# Cisco-Console-CP2102-Piggyback-v2.net
KiCad netlist of a schematic drawn in EAGLE
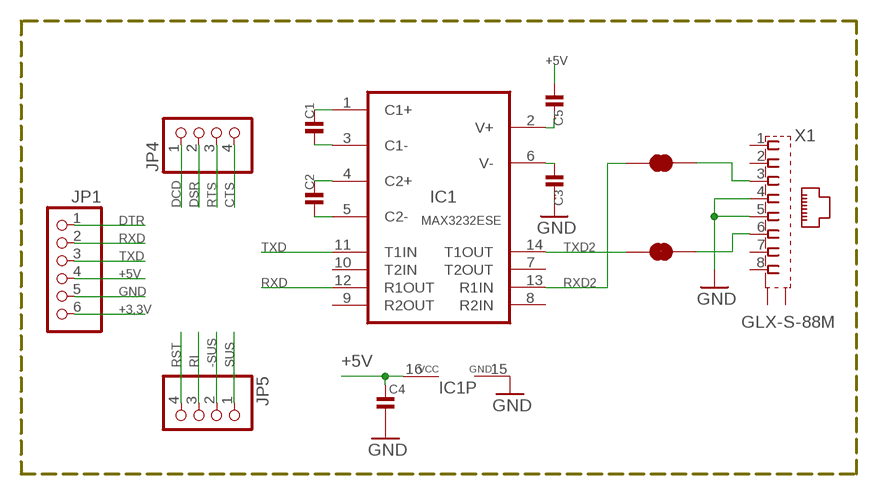
[diagram p0: schematic, sheet 1]

(export (version "E")
  (design (tool "Eeschema 10.0.6"))
  (components
    (comp (ref "C1")
      (value "MICROBUILDER_CAP_CERAMIC0402")
      (footprint "eagle-import:MICROBUILDER_0402")
      (libsource (lib "eagle-import") (part "MICROBUILDER_CAP_CERAMIC0402"))
    )
    (comp (ref "C2")
      (value "MICROBUILDER_CAP_CERAMIC0402")
      (footprint "eagle-import:MICROBUILDER_0402")
      (libsource (lib "eagle-import") (part "MICROBUILDER_CAP_CERAMIC0402"))
    )
    (comp (ref "C3")
      (value "MICROBUILDER_CAP_CERAMIC0402")
      (footprint "eagle-import:MICROBUILDER_0402")
      (libsource (lib "eagle-import") (part "MICROBUILDER_CAP_CERAMIC0402"))
    )
    (comp (ref "C4")
      (value "MICROBUILDER_CAP_CERAMIC0402")
      (footprint "eagle-import:MICROBUILDER_0402")
      (libsource (lib "eagle-import") (part "MICROBUILDER_CAP_CERAMIC0402"))
    )
    (comp (ref "C5")
      (value "MICROBUILDER_CAP_CERAMIC0402")
      (footprint "eagle-import:MICROBUILDER_0402")
      (libsource (lib "eagle-import") (part "MICROBUILDER_CAP_CERAMIC0402"))
    )
    (comp (ref "IC1")
      (value "MAX3232ESE")
      (footprint "eagle-import:SO16")
      (fields (field (name "MF") "MAXIM"))
      (libsource (lib "eagle-import") (part "MAX3232SEE"))
    )
    (comp (ref "JP1")
      (value "PINHD-1X6")
      (footprint "eagle-import:1X06")
      (libsource (lib "eagle-import") (part "PINHD-1X6"))
    )
    (comp (ref "JP4")
      (value "PINHD-1X4")
      (footprint "eagle-import:1X04")
      (libsource (lib "eagle-import") (part "PINHD-1X4"))
    )
    (comp (ref "JP5")
      (value "PINHD-1X4")
      (footprint "eagle-import:1X04")
      (libsource (lib "eagle-import") (part "PINHD-1X4"))
    )
    (comp (ref "JP6")
      (value "JUMPER-SMT_2_NC_TRACE_NO-SILK")
      (footprint "eagle-import:SMT-JUMPER_2_NC_TRACE_NO-SILK")
      (libsource (lib "eagle-import") (part "JUMPER-SMT_2_NC_TRACE_NO-SILK"))
    )
    (comp (ref "JP9")
      (value "JUMPER-SMT_2_NC_TRACE_NO-SILK")
      (footprint "eagle-import:SMT-JUMPER_2_NC_TRACE_NO-SILK")
      (libsource (lib "eagle-import") (part "JUMPER-SMT_2_NC_TRACE_NO-SILK"))
    )
    (comp (ref "X1")
      (value "GLX-S-88M")
      (footprint "eagle-import:GLX-S-88M")
      (libsource (lib "eagle-import") (part "GLX-S-88M"))
    )
  )
  (nets
    (net (code "1") (name "/+3,3V") (class "Default")
      (node (ref "JP1") (pin "6") (pinfunction "6_6") (pintype "passive"))
    )
    (net (code "2") (name "/+5V") (class "Default")
      (node (ref "C4") (pin "1") (pinfunction "P$1_1") (pintype "passive"))
      (node (ref "C5") (pin "1") (pinfunction "P$1_1") (pintype "passive"))
      (node (ref "IC1") (pin "16") (pinfunction "VCC_16") (pintype "power_in"))
      (node (ref "JP1") (pin "4") (pinfunction "4_4") (pintype "passive"))
    )
    (net (code "3") (name "/-SUS") (class "Default")
      (node (ref "JP5") (pin "2") (pinfunction "2_2") (pintype "passive"))
    )
    (net (code "4") (name "/CTS") (class "Default")
      (node (ref "JP4") (pin "4") (pinfunction "4_4") (pintype "passive"))
    )
    (net (code "5") (name "/DCD") (class "Default")
      (node (ref "JP4") (pin "1") (pinfunction "1_1") (pintype "passive"))
    )
    (net (code "6") (name "/DSR") (class "Default")
      (node (ref "JP4") (pin "2") (pinfunction "2_2") (pintype "passive"))
    )
    (net (code "7") (name "/DTR") (class "Default")
      (node (ref "JP1") (pin "1") (pinfunction "1_1") (pintype "passive"))
    )
    (net (code "8") (name "/RI") (class "Default")
      (node (ref "JP5") (pin "3") (pinfunction "3_3") (pintype "passive"))
    )
    (net (code "9") (name "/RST") (class "Default")
      (node (ref "JP5") (pin "4") (pinfunction "4_4") (pintype "passive"))
    )
    (net (code "10") (name "/RTS") (class "Default")
      (node (ref "JP4") (pin "3") (pinfunction "3_3") (pintype "passive"))
    )
    (net (code "11") (name "/RXD") (class "Default")
      (node (ref "IC1") (pin "12") (pinfunction "R1OUT_12") (pintype "output"))
      (node (ref "JP1") (pin "2") (pinfunction "2_2") (pintype "passive"))
    )
    (net (code "12") (name "/RXD2") (class "Default")
      (node (ref "IC1") (pin "13") (pinfunction "R1IN_13") (pintype "input"))
      (node (ref "JP6") (pin "1") (pinfunction "1_1") (pintype "passive"))
    )
    (net (code "13") (name "/SUS") (class "Default")
      (node (ref "JP5") (pin "1") (pinfunction "1_1") (pintype "passive"))
    )
    (net (code "14") (name "/TXD") (class "Default")
      (node (ref "IC1") (pin "11") (pinfunction "T1IN_11") (pintype "input"))
      (node (ref "JP1") (pin "3") (pinfunction "3_3") (pintype "passive"))
    )
    (net (code "15") (name "/TXD2") (class "Default")
      (node (ref "IC1") (pin "14") (pinfunction "T1OUT_14") (pintype "output"))
      (node (ref "JP9") (pin "1") (pinfunction "1_1") (pintype "passive"))
    )
    (net (code "16") (name "GND") (class "Default")
      (node (ref "C3") (pin "2") (pinfunction "P$2_2") (pintype "passive"))
      (node (ref "C4") (pin "2") (pinfunction "P$2_2") (pintype "passive"))
      (node (ref "IC1") (pin "15") (pinfunction "GND_15") (pintype "power_in"))
      (node (ref "JP1") (pin "5") (pinfunction "5_5") (pintype "passive"))
      (node (ref "X1") (pin "4") (pinfunction "4_4") (pintype "passive"))
      (node (ref "X1") (pin "5") (pinfunction "5_5") (pintype "passive"))
    )
    (net (code "17") (name "Net-(C1-P$1)") (class "Default")
      (node (ref "C1") (pin "1") (pinfunction "P$1_1") (pintype "passive"))
      (node (ref "IC1") (pin "1") (pinfunction "C1+_1") (pintype "bidirectional"))
    )
    (net (code "18") (name "Net-(C1-P$2)") (class "Default")
      (node (ref "C1") (pin "2") (pinfunction "P$2_2") (pintype "passive"))
      (node (ref "IC1") (pin "3") (pinfunction "C1-_3") (pintype "bidirectional"))
    )
    (net (code "19") (name "Net-(C2-P$1)") (class "Default")
      (node (ref "C2") (pin "1") (pinfunction "P$1_1") (pintype "passive"))
      (node (ref "IC1") (pin "4") (pinfunction "C2+_4") (pintype "bidirectional"))
    )
    (net (code "20") (name "Net-(C2-P$2)") (class "Default")
      (node (ref "C2") (pin "2") (pinfunction "P$2_2") (pintype "passive"))
      (node (ref "IC1") (pin "5") (pinfunction "C2-_5") (pintype "bidirectional"))
    )
    (net (code "21") (name "Net-(C3-P$1)") (class "Default")
      (node (ref "C3") (pin "1") (pinfunction "P$1_1") (pintype "passive"))
      (node (ref "IC1") (pin "6") (pinfunction "V-_6") (pintype "bidirectional"))
    )
    (net (code "22") (name "Net-(C5-P$2)") (class "Default")
      (node (ref "C5") (pin "2") (pinfunction "P$2_2") (pintype "passive"))
      (node (ref "IC1") (pin "2") (pinfunction "V+_2") (pintype "bidirectional"))
    )
    (net (code "23") (name "Net-(JP6-Pad2)") (class "Default")
      (node (ref "JP6") (pin "2") (pinfunction "2_2") (pintype "passive"))
      (node (ref "X1") (pin "3") (pinfunction "3_3") (pintype "passive"))
    )
    (net (code "24") (name "Net-(JP9-Pad2)") (class "Default")
      (node (ref "JP9") (pin "2") (pinfunction "2_2") (pintype "passive"))
      (node (ref "X1") (pin "6") (pinfunction "6_6") (pintype "passive"))
    )
    (net (code "25") (name "unconnected-(IC1A-R2IN-Pad8)") (class "Default")
      (node (ref "IC1") (pin "8") (pinfunction "R2IN_8") (pintype "input"))
    )
    (net (code "26") (name "unconnected-(IC1A-R2OUT-Pad9)") (class "Default")
      (node (ref "IC1") (pin "9") (pinfunction "R2OUT_9") (pintype "output"))
    )
    (net (code "27") (name "unconnected-(IC1A-T2IN-Pad10)") (class "Default")
      (node (ref "IC1") (pin "10") (pinfunction "T2IN_10") (pintype "input"))
    )
    (net (code "28") (name "unconnected-(IC1A-T2OUT-Pad7)") (class "Default")
      (node (ref "IC1") (pin "7") (pinfunction "T2OUT_7") (pintype "output"))
    )
    (net (code "29") (name "unconnected-(X1-Pad1)") (class "Default")
      (node (ref "X1") (pin "1") (pinfunction "1_1") (pintype "passive"))
    )
    (net (code "30") (name "unconnected-(X1-Pad2)") (class "Default")
      (node (ref "X1") (pin "2") (pinfunction "2_2") (pintype "passive"))
    )
    (net (code "31") (name "unconnected-(X1-Pad7)") (class "Default")
      (node (ref "X1") (pin "7") (pinfunction "7_7") (pintype "passive"))
    )
    (net (code "32") (name "unconnected-(X1-Pad8)") (class "Default")
      (node (ref "X1") (pin "8") (pinfunction "8_8") (pintype "passive"))
    )
    (net (code "33") (name "unconnected-(X1-PadS1)") (class "Default")
      (node (ref "X1") (pin "S1") (pinfunction "S1_S1") (pintype "passive"))
    )
    (net (code "34") (name "unconnected-(X1-PadS2)") (class "Default")
      (node (ref "X1") (pin "S2") (pinfunction "S2_S2") (pintype "passive"))
    )
  )
)
